# Robot.net
KiCad netlist of a schematic drawn in Altium Designer
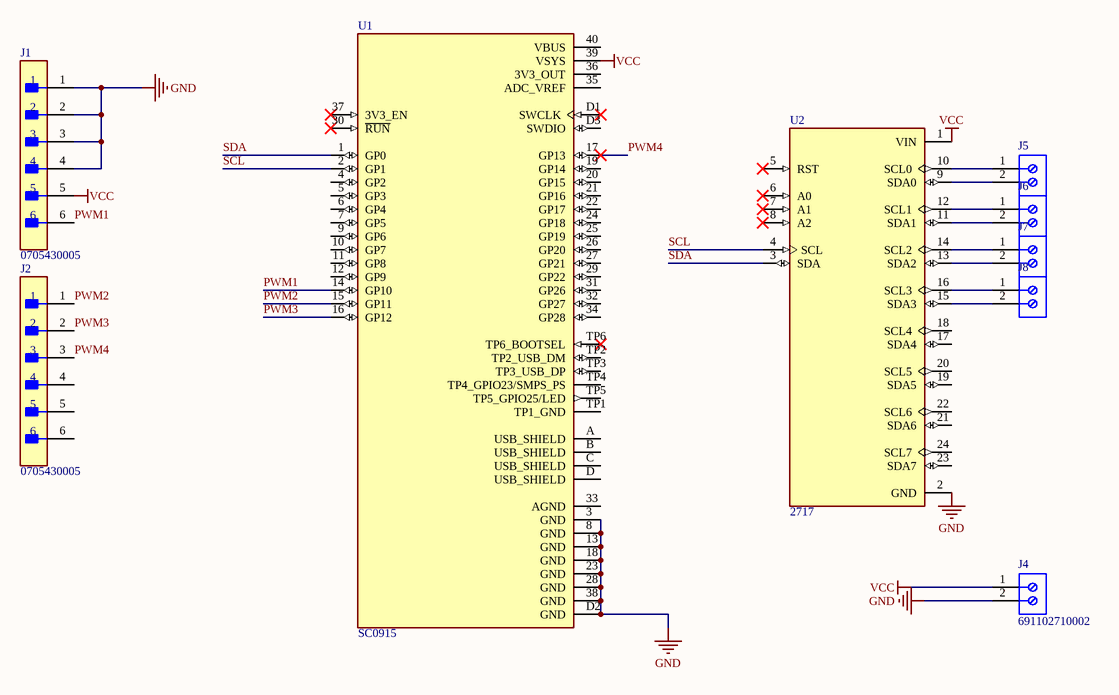
[diagram p0: Robot.SchDoc]

(export (version "E")
  (design (tool "Eeschema 10.0.6"))
  (components
    (comp (ref "J1")
      (value "0705430005")
      (footprint "FP-0705430005-MFG")
      (description "Conn Shrouded Header HDR 6 POS 2.54mm Solder ST Thru-Hole SL™ Tube")
      (fields (field (name "OCTOPART") "https://octopart.com/70543-0005-molex-12981"))
      (libsource (lib "Altium Content Vault") (part "f2cb566baf1c37ab5a3b8e90bbeafd6"))
    )
    (comp (ref "J2")
      (value "0705430005")
      (footprint "FP-0705430005-MFG")
      (description "Conn Shrouded Header HDR 6 POS 2.54mm Solder ST Thru-Hole SL™ Tube")
      (fields (field (name "OCTOPART") "https://octopart.com/70543-0005-molex-12981"))
      (libsource (lib "Altium Content Vault") (part "f2cb566baf1c37ab5a3b8e90bbeafd6"))
    )
    (comp (ref "J4")
      (value "691102710002")
      (footprint "691102710002")
      (fields (field (name "VOLTAGE") "300V"))
      (libsource (lib "Altium Content Vault") (part "TBL - 1R - 02P - Screw"))
    )
    (comp (ref "J5")
      (value "691102710002")
      (footprint "691102710002")
      (fields (field (name "VOLTAGE") "300V"))
      (libsource (lib "Altium Content Vault") (part "TBL - 1R - 02P - Screw"))
    )
    (comp (ref "J6")
      (value "691102710002")
      (footprint "691102710002")
      (fields (field (name "VOLTAGE") "300V"))
      (libsource (lib "Altium Content Vault") (part "TBL - 1R - 02P - Screw"))
    )
    (comp (ref "J7")
      (value "691102710002")
      (footprint "691102710002")
      (fields (field (name "VOLTAGE") "300V"))
      (libsource (lib "Altium Content Vault") (part "TBL - 1R - 02P - Screw"))
    )
    (comp (ref "J8")
      (value "691102710002")
      (footprint "691102710002")
      (fields (field (name "VOLTAGE") "300V"))
      (libsource (lib "Altium Content Vault") (part "TBL - 1R - 02P - Screw"))
    )
    (comp (ref "U1")
      (value "SC0915")
      (footprint "MODULE_SC0915")
      (description "RP2040 Raspberry Pi Pico series ARMÂ® CortexÂ®-M0+ MCU 32-Bit Embedded Evaluation Board")
      (fields (field (name "MF") "Raspberry Pi"))
      (libsource (lib "Diseño de productos electrónicos 2023-2") (part "SC0915"))
    )
    (comp (ref "U2")
      (value "2717")
      (footprint "MODULE_2717")
      (description "Module: multiplexer; I2C interface multiplexer; TCA9548A; 3Ã·5VDC")
      (fields (field (name "MF") "Adafruit"))
      (libsource (lib "Diseño de productos electrónicos 2023-2") (part "2717"))
    )
  )
  (nets
    (net (code "1") (name "/PWM1") (class "Default")
      (node (ref "J1") (pin "6") (pinfunction "6_6") (pintype "passive"))
      (node (ref "U1") (pin "14") (pinfunction "GP10_14") (pintype "bidirectional"))
    )
    (net (code "2") (name "/PWM2") (class "Default")
      (node (ref "J2") (pin "1") (pinfunction "1_1") (pintype "passive"))
      (node (ref "U1") (pin "15") (pinfunction "GP11_15") (pintype "bidirectional"))
    )
    (net (code "3") (name "/PWM3") (class "Default")
      (node (ref "J2") (pin "2") (pinfunction "2_2") (pintype "passive"))
      (node (ref "U1") (pin "16") (pinfunction "GP12_16") (pintype "bidirectional"))
    )
    (net (code "4") (name "/PWM4") (class "Default")
      (node (ref "J2") (pin "3") (pinfunction "3_3") (pintype "passive"))
      (node (ref "U1") (pin "17") (pinfunction "GP13_17") (pintype "bidirectional"))
    )
    (net (code "5") (name "/SCL") (class "Default")
      (node (ref "U1") (pin "2") (pinfunction "GP1_2") (pintype "bidirectional"))
      (node (ref "U2") (pin "4") (pinfunction "SCL_4") (pintype "input"))
    )
    (net (code "6") (name "/SDA") (class "Default")
      (node (ref "U1") (pin "1") (pinfunction "GP0_1") (pintype "bidirectional"))
      (node (ref "U2") (pin "3") (pinfunction "SDA_3") (pintype "bidirectional"))
    )
    (net (code "7") (name "GND") (class "Default")
      (node (ref "J1") (pin "1") (pinfunction "1_1") (pintype "passive"))
      (node (ref "J1") (pin "2") (pinfunction "2_2") (pintype "passive"))
      (node (ref "J1") (pin "3") (pinfunction "3_3") (pintype "passive"))
      (node (ref "J1") (pin "4") (pinfunction "4_4") (pintype "passive"))
      (node (ref "J4") (pin "2") (pinfunction "2_2") (pintype "passive"))
      (node (ref "U1") (pin "13") (pinfunction "GND_13") (pintype "power_in"))
      (node (ref "U1") (pin "18") (pinfunction "GND_18") (pintype "power_in"))
      (node (ref "U1") (pin "23") (pinfunction "GND_23") (pintype "power_in"))
      (node (ref "U1") (pin "28") (pinfunction "GND_28") (pintype "power_in"))
      (node (ref "U1") (pin "3") (pinfunction "GND_3") (pintype "power_in"))
      (node (ref "U1") (pin "38") (pinfunction "GND_38") (pintype "power_in"))
      (node (ref "U1") (pin "8") (pinfunction "GND_8") (pintype "power_in"))
      (node (ref "U1") (pin "D2") (pinfunction "GND_D2") (pintype "power_in"))
      (node (ref "U2") (pin "2") (pinfunction "GND_2") (pintype "power_in"))
    )
    (net (code "8") (name "Net-(U2-SCL0)") (class "Default")
      (node (ref "J5") (pin "1") (pinfunction "1_1") (pintype "passive"))
      (node (ref "U2") (pin "10") (pinfunction "SCL0_10") (pintype "output"))
    )
    (net (code "9") (name "Net-(U2-SCL1)") (class "Default")
      (node (ref "J6") (pin "1") (pinfunction "1_1") (pintype "passive"))
      (node (ref "U2") (pin "12") (pinfunction "SCL1_12") (pintype "output"))
    )
    (net (code "10") (name "Net-(U2-SCL2)") (class "Default")
      (node (ref "J7") (pin "1") (pinfunction "1_1") (pintype "passive"))
      (node (ref "U2") (pin "14") (pinfunction "SCL2_14") (pintype "output"))
    )
    (net (code "11") (name "Net-(U2-SCL3)") (class "Default")
      (node (ref "J8") (pin "1") (pinfunction "1_1") (pintype "passive"))
      (node (ref "U2") (pin "16") (pinfunction "SCL3_16") (pintype "output"))
    )
    (net (code "12") (name "Net-(U2-SDA0)") (class "Default")
      (node (ref "J5") (pin "2") (pinfunction "2_2") (pintype "passive"))
      (node (ref "U2") (pin "9") (pinfunction "SDA0_9") (pintype "bidirectional"))
    )
    (net (code "13") (name "Net-(U2-SDA1)") (class "Default")
      (node (ref "J6") (pin "2") (pinfunction "2_2") (pintype "passive"))
      (node (ref "U2") (pin "11") (pinfunction "SDA1_11") (pintype "bidirectional"))
    )
    (net (code "14") (name "Net-(U2-SDA2)") (class "Default")
      (node (ref "J7") (pin "2") (pinfunction "2_2") (pintype "passive"))
      (node (ref "U2") (pin "13") (pinfunction "SDA2_13") (pintype "bidirectional"))
    )
    (net (code "15") (name "Net-(U2-SDA3)") (class "Default")
      (node (ref "J8") (pin "2") (pinfunction "2_2") (pintype "passive"))
      (node (ref "U2") (pin "15") (pinfunction "SDA3_15") (pintype "bidirectional"))
    )
    (net (code "16") (name "VCC") (class "Default")
      (node (ref "J1") (pin "5") (pinfunction "5_5") (pintype "passive"))
      (node (ref "J4") (pin "1") (pinfunction "1_1") (pintype "passive"))
      (node (ref "U1") (pin "39") (pinfunction "VSYS_39") (pintype "power_in"))
      (node (ref "U2") (pin "1") (pinfunction "VIN_1") (pintype "power_in"))
    )
    (net (code "17") (name "unconnected-(J2-Pad4)") (class "Default")
      (node (ref "J2") (pin "4") (pinfunction "4_4") (pintype "passive"))
    )
    (net (code "18") (name "unconnected-(J2-Pad5)") (class "Default")
      (node (ref "J2") (pin "5") (pinfunction "5_5") (pintype "passive"))
    )
    (net (code "19") (name "unconnected-(J2-Pad6)") (class "Default")
      (node (ref "J2") (pin "6") (pinfunction "6_6") (pintype "passive"))
    )
    (net (code "20") (name "unconnected-(U1-3V3_EN-Pad37)") (class "Default")
      (node (ref "U1") (pin "37") (pinfunction "3V3_EN_37") (pintype "input+no_connect"))
    )
    (net (code "21") (name "unconnected-(U1-3V3_OUT-Pad36)") (class "Default")
      (node (ref "U1") (pin "36") (pinfunction "3V3_OUT_36") (pintype "power_in"))
    )
    (net (code "22") (name "unconnected-(U1-ADC_VREF-Pad35)") (class "Default")
      (node (ref "U1") (pin "35") (pinfunction "ADC_VREF_35") (pintype "power_in"))
    )
    (net (code "23") (name "unconnected-(U1-AGND-Pad33)") (class "Default")
      (node (ref "U1") (pin "33") (pinfunction "AGND_33") (pintype "power_in"))
    )
    (net (code "24") (name "unconnected-(U1-GP2-Pad4)") (class "Default")
      (node (ref "U1") (pin "4") (pinfunction "GP2_4") (pintype "bidirectional"))
    )
    (net (code "25") (name "unconnected-(U1-GP3-Pad5)") (class "Default")
      (node (ref "U1") (pin "5") (pinfunction "GP3_5") (pintype "bidirectional"))
    )
    (net (code "26") (name "unconnected-(U1-GP4-Pad6)") (class "Default")
      (node (ref "U1") (pin "6") (pinfunction "GP4_6") (pintype "bidirectional"))
    )
    (net (code "27") (name "unconnected-(U1-GP5-Pad7)") (class "Default")
      (node (ref "U1") (pin "7") (pinfunction "GP5_7") (pintype "bidirectional"))
    )
    (net (code "28") (name "unconnected-(U1-GP6-Pad9)") (class "Default")
      (node (ref "U1") (pin "9") (pinfunction "GP6_9") (pintype "bidirectional"))
    )
    (net (code "29") (name "unconnected-(U1-GP7-Pad10)") (class "Default")
      (node (ref "U1") (pin "10") (pinfunction "GP7_10") (pintype "bidirectional"))
    )
    (net (code "30") (name "unconnected-(U1-GP8-Pad11)") (class "Default")
      (node (ref "U1") (pin "11") (pinfunction "GP8_11") (pintype "bidirectional"))
    )
    (net (code "31") (name "unconnected-(U1-GP9-Pad12)") (class "Default")
      (node (ref "U1") (pin "12") (pinfunction "GP9_12") (pintype "bidirectional"))
    )
    (net (code "32") (name "unconnected-(U1-GP14-Pad19)") (class "Default")
      (node (ref "U1") (pin "19") (pinfunction "GP14_19") (pintype "bidirectional"))
    )
    (net (code "33") (name "unconnected-(U1-GP15-Pad20)") (class "Default")
      (node (ref "U1") (pin "20") (pinfunction "GP15_20") (pintype "bidirectional"))
    )
    (net (code "34") (name "unconnected-(U1-GP16-Pad21)") (class "Default")
      (node (ref "U1") (pin "21") (pinfunction "GP16_21") (pintype "bidirectional"))
    )
    (net (code "35") (name "unconnected-(U1-GP17-Pad22)") (class "Default")
      (node (ref "U1") (pin "22") (pinfunction "GP17_22") (pintype "bidirectional"))
    )
    (net (code "36") (name "unconnected-(U1-GP18-Pad24)") (class "Default")
      (node (ref "U1") (pin "24") (pinfunction "GP18_24") (pintype "bidirectional"))
    )
    (net (code "37") (name "unconnected-(U1-GP19-Pad25)") (class "Default")
      (node (ref "U1") (pin "25") (pinfunction "GP19_25") (pintype "bidirectional"))
    )
    (net (code "38") (name "unconnected-(U1-GP20-Pad26)") (class "Default")
      (node (ref "U1") (pin "26") (pinfunction "GP20_26") (pintype "bidirectional"))
    )
    (net (code "39") (name "unconnected-(U1-GP21-Pad27)") (class "Default")
      (node (ref "U1") (pin "27") (pinfunction "GP21_27") (pintype "bidirectional"))
    )
    (net (code "40") (name "unconnected-(U1-GP22-Pad29)") (class "Default")
      (node (ref "U1") (pin "29") (pinfunction "GP22_29") (pintype "bidirectional"))
    )
    (net (code "41") (name "unconnected-(U1-GP26-Pad31)") (class "Default")
      (node (ref "U1") (pin "31") (pinfunction "GP26_31") (pintype "bidirectional"))
    )
    (net (code "42") (name "unconnected-(U1-GP27-Pad32)") (class "Default")
      (node (ref "U1") (pin "32") (pinfunction "GP27_32") (pintype "bidirectional"))
    )
    (net (code "43") (name "unconnected-(U1-GP28-Pad34)") (class "Default")
      (node (ref "U1") (pin "34") (pinfunction "GP28_34") (pintype "bidirectional"))
    )
    (net (code "44") (name "unconnected-(U1-SWCLK-PadD1)") (class "Default")
      (node (ref "U1") (pin "D1") (pinfunction "SWCLK_D1") (pintype "input+no_connect"))
    )
    (net (code "45") (name "unconnected-(U1-SWDIO-PadD3)") (class "Default")
      (node (ref "U1") (pin "D3") (pinfunction "SWDIO_D3") (pintype "bidirectional"))
    )
    (net (code "46") (name "unconnected-(U1-TP1_GND-PadTP1)") (class "Default")
      (node (ref "U1") (pin "TP1") (pinfunction "TP1_GND_TP1") (pintype "power_in"))
    )
    (net (code "47") (name "unconnected-(U1-TP2_USB_DM-PadTP2)") (class "Default")
      (node (ref "U1") (pin "TP2") (pinfunction "TP2_USB_DM_TP2") (pintype "bidirectional"))
    )
    (net (code "48") (name "unconnected-(U1-TP3_USB_DP-PadTP3)") (class "Default")
      (node (ref "U1") (pin "TP3") (pinfunction "TP3_USB_DP_TP3") (pintype "bidirectional"))
    )
    (net (code "49") (name "unconnected-(U1-TP4_GPIO23{slash}SMPS_PS-PadTP4)") (class "Default")
      (node (ref "U1") (pin "TP4") (pinfunction "TP4_GPIO23/SMPS_PS_TP4") (pintype "passive"))
    )
    (net (code "50") (name "unconnected-(U1-TP5_GPIO25{slash}LED-PadTP5)") (class "Default")
      (node (ref "U1") (pin "TP5") (pinfunction "TP5_GPIO25/LED_TP5") (pintype "output"))
    )
    (net (code "51") (name "unconnected-(U1-TP6_BOOTSEL-PadTP6)") (class "Default")
      (node (ref "U1") (pin "TP6") (pinfunction "TP6_BOOTSEL_TP6") (pintype "input+no_connect"))
    )
    (net (code "52") (name "unconnected-(U1-USB_SHIELD-PadA)") (class "Default")
      (node (ref "U1") (pin "A") (pinfunction "USB_SHIELD_A") (pintype "power_in"))
    )
    (net (code "53") (name "unconnected-(U1-USB_SHIELD-PadB)") (class "Default")
      (node (ref "U1") (pin "B") (pinfunction "USB_SHIELD_B") (pintype "power_in"))
    )
    (net (code "54") (name "unconnected-(U1-USB_SHIELD-PadC)") (class "Default")
      (node (ref "U1") (pin "C") (pinfunction "USB_SHIELD_C") (pintype "power_in"))
    )
    (net (code "55") (name "unconnected-(U1-USB_SHIELD-PadD)") (class "Default")
      (node (ref "U1") (pin "D") (pinfunction "USB_SHIELD_D") (pintype "power_in"))
    )
    (net (code "56") (name "unconnected-(U1-VBUS-Pad40)") (class "Default")
      (node (ref "U1") (pin "40") (pinfunction "VBUS_40") (pintype "power_in"))
    )
    (net (code "57") (name "unconnected-(U1-~{RUN}-Pad30)") (class "Default")
      (node (ref "U1") (pin "30") (pinfunction "~{RUN}_30") (pintype "input+no_connect"))
    )
    (net (code "58") (name "unconnected-(U2-A0-Pad6)") (class "Default")
      (node (ref "U2") (pin "6") (pinfunction "A0_6") (pintype "input+no_connect"))
    )
    (net (code "59") (name "unconnected-(U2-A1-Pad7)") (class "Default")
      (node (ref "U2") (pin "7") (pinfunction "A1_7") (pintype "input+no_connect"))
    )
    (net (code "60") (name "unconnected-(U2-A2-Pad8)") (class "Default")
      (node (ref "U2") (pin "8") (pinfunction "A2_8") (pintype "input+no_connect"))
    )
    (net (code "61") (name "unconnected-(U2-RST-Pad5)") (class "Default")
      (node (ref "U2") (pin "5") (pinfunction "RST_5") (pintype "input+no_connect"))
    )
    (net (code "62") (name "unconnected-(U2-SCL4-Pad18)") (class "Default")
      (node (ref "U2") (pin "18") (pinfunction "SCL4_18") (pintype "output"))
    )
    (net (code "63") (name "unconnected-(U2-SCL5-Pad20)") (class "Default")
      (node (ref "U2") (pin "20") (pinfunction "SCL5_20") (pintype "output"))
    )
    (net (code "64") (name "unconnected-(U2-SCL6-Pad22)") (class "Default")
      (node (ref "U2") (pin "22") (pinfunction "SCL6_22") (pintype "output"))
    )
    (net (code "65") (name "unconnected-(U2-SCL7-Pad24)") (class "Default")
      (node (ref "U2") (pin "24") (pinfunction "SCL7_24") (pintype "output"))
    )
    (net (code "66") (name "unconnected-(U2-SDA4-Pad17)") (class "Default")
      (node (ref "U2") (pin "17") (pinfunction "SDA4_17") (pintype "bidirectional"))
    )
    (net (code "67") (name "unconnected-(U2-SDA5-Pad19)") (class "Default")
      (node (ref "U2") (pin "19") (pinfunction "SDA5_19") (pintype "bidirectional"))
    )
    (net (code "68") (name "unconnected-(U2-SDA6-Pad21)") (class "Default")
      (node (ref "U2") (pin "21") (pinfunction "SDA6_21") (pintype "bidirectional"))
    )
    (net (code "69") (name "unconnected-(U2-SDA7-Pad23)") (class "Default")
      (node (ref "U2") (pin "23") (pinfunction "SDA7_23") (pintype "bidirectional"))
    )
  )
)
